# 2228_Emetteur_Alimentation.net
KiCad netlist of a schematic drawn in Altium Designer
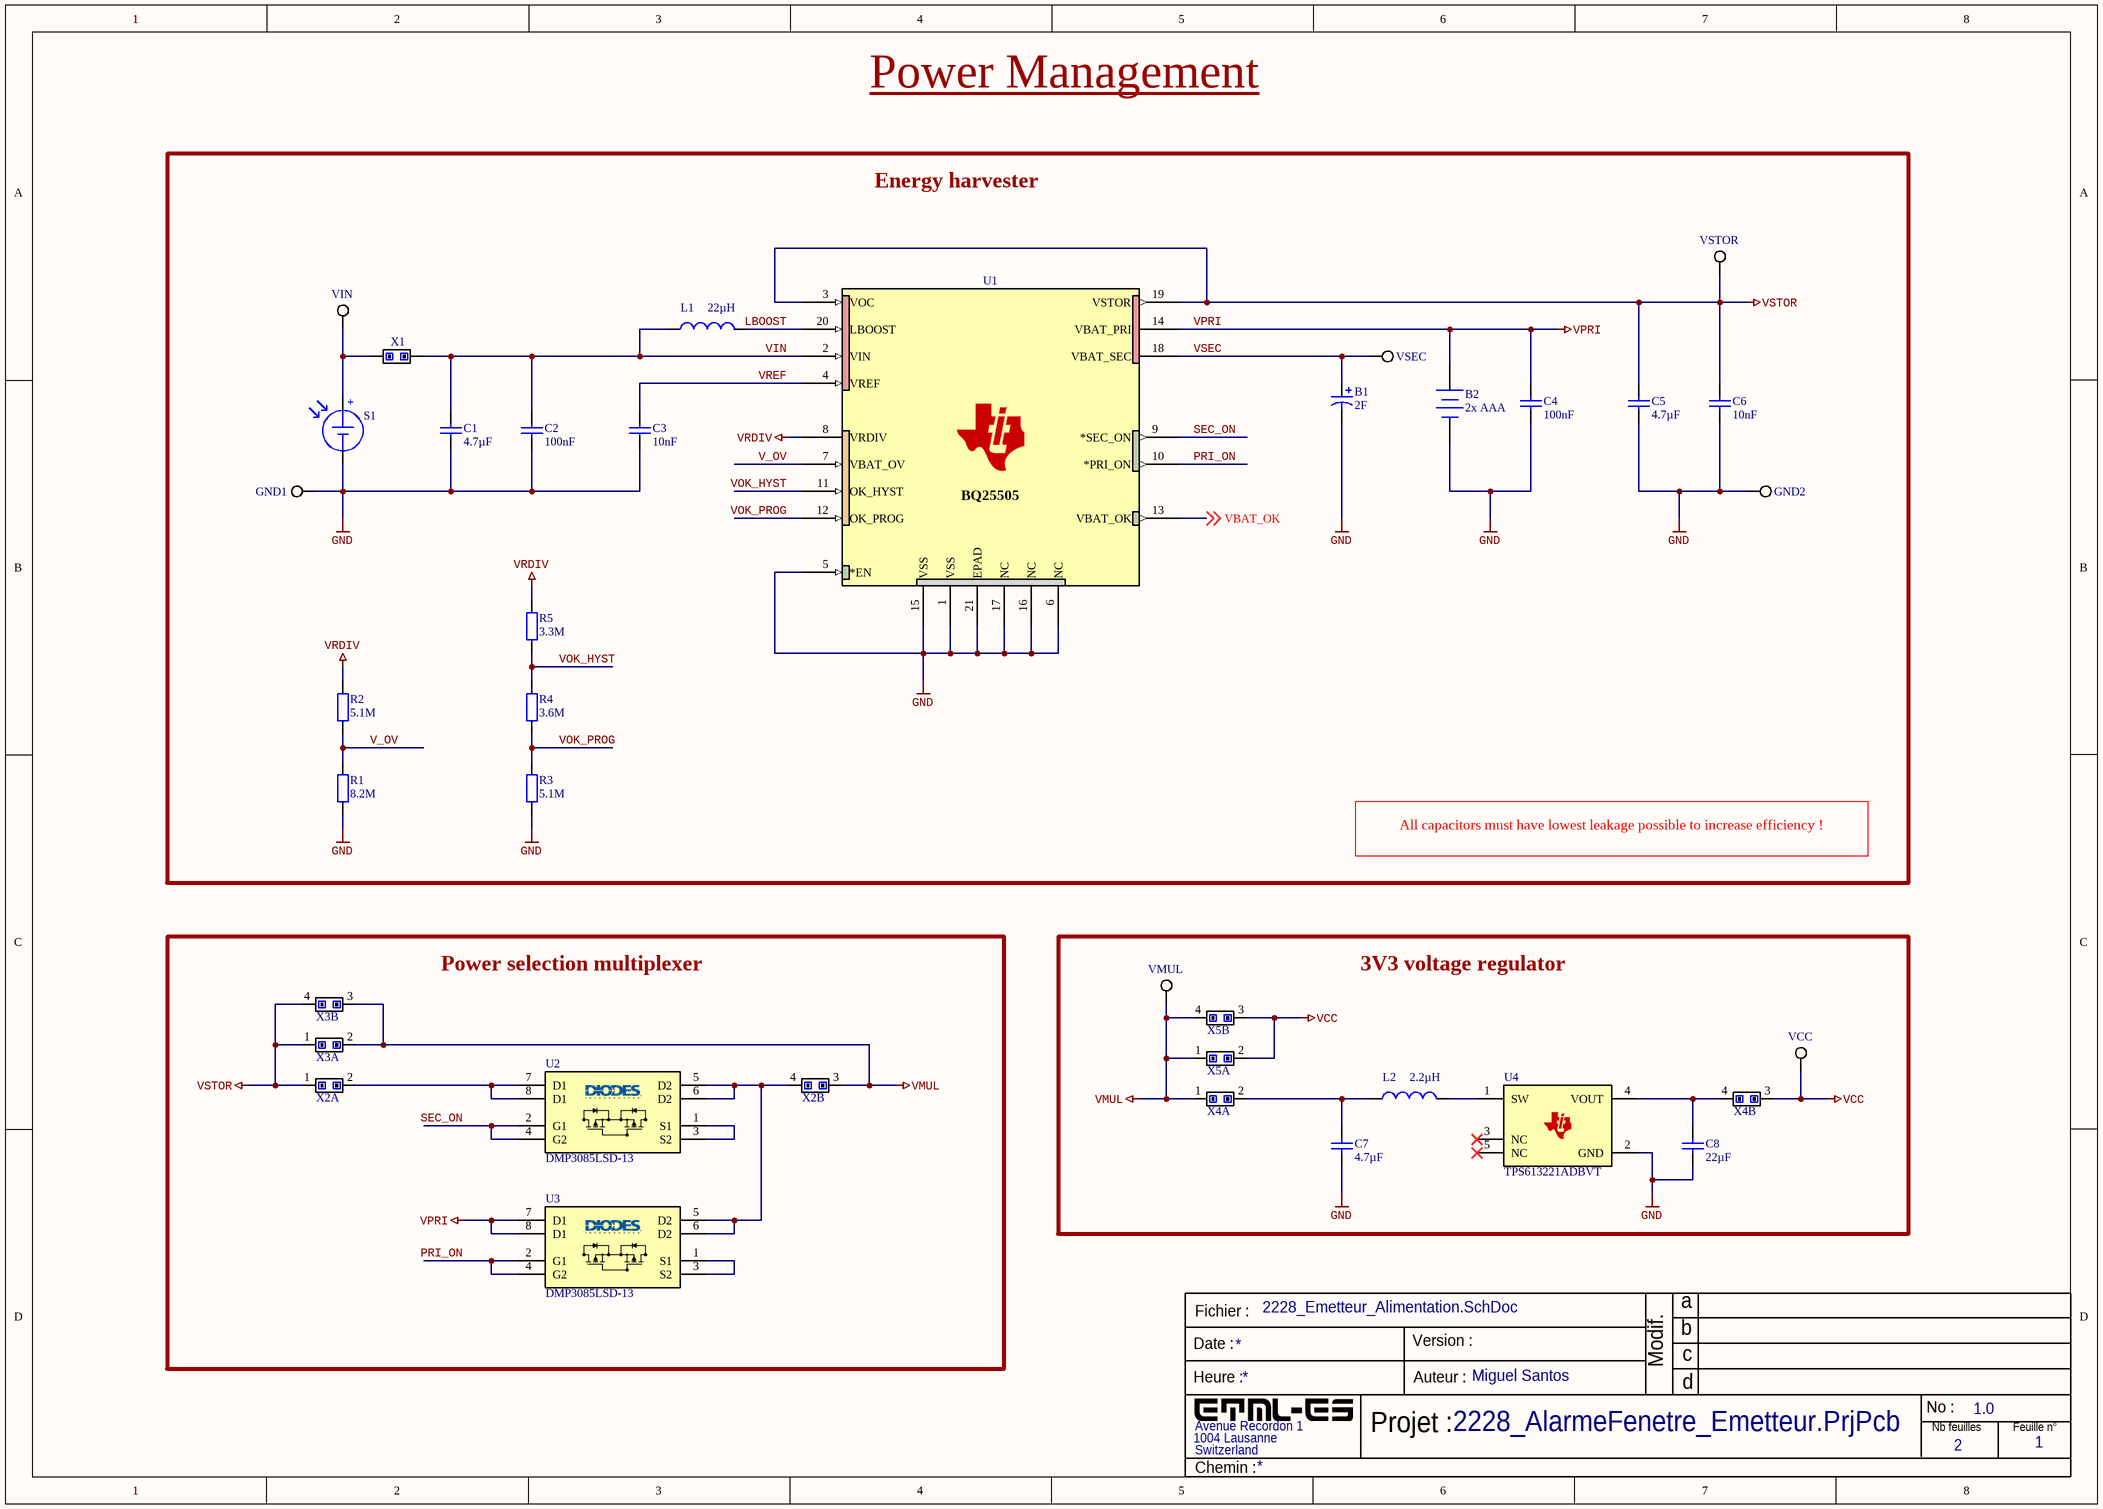
[diagram p0: 2228_Emetteur_Alimentation.SchDoc]

(export (version "E")
  (design (tool "Eeschema 10.0.6"))
  (components
    (comp (ref "B1")
      (value "2F")
      (footprint "2228_AlarmeFenetre_Footprints:SuperCap")
      (description "Polarized SuperCapacitor (Radial)")
      (fields (field (name "Comment") "SUPERCAP"))
      (libsource (lib "2228_AlarmeFenetre_Symbols") (part "SUPERCAP"))
    )
    (comp (ref "B2")
      (value "2x AAA")
      (footprint "WE_2PINS")
      (description "Multicell Battery")
      (libsource (lib "2228_AlarmeFenetre_Symbols") (part "Battery"))
    )
    (comp (ref "C1")
      (value "4.7µF")
      (footprint "CAP_0805")
      (description "Capacitor")
      (fields (field (name "Comment") "CAP_SMD"))
      (libsource (lib "2228_AlarmeFenetre_Symbols") (part "CAP_SMD"))
    )
    (comp (ref "C2")
      (value "100nF")
      (footprint "CAP_0805")
      (description "Capacitor")
      (fields (field (name "Comment") "CAP_SMD"))
      (libsource (lib "2228_AlarmeFenetre_Symbols") (part "CAP_SMD"))
    )
    (comp (ref "C3")
      (value "10nF")
      (footprint "CAP_0805")
      (description "Capacitor")
      (fields (field (name "Comment") "CAP_SMD"))
      (libsource (lib "2228_AlarmeFenetre_Symbols") (part "CAP_SMD"))
    )
    (comp (ref "C4")
      (value "100nF")
      (footprint "CAP_0805")
      (description "Capacitor")
      (fields (field (name "Comment") "CAP_SMD"))
      (libsource (lib "2228_AlarmeFenetre_Symbols") (part "CAP_SMD"))
    )
    (comp (ref "C5")
      (value "4.7µF")
      (footprint "CAP_0805")
      (description "Capacitor")
      (fields (field (name "Comment") "CAP_SMD"))
      (libsource (lib "2228_AlarmeFenetre_Symbols") (part "CAP_SMD"))
    )
    (comp (ref "C6")
      (value "10nF")
      (footprint "CAP_0805")
      (description "Capacitor")
      (fields (field (name "Comment") "CAP_SMD"))
      (libsource (lib "2228_AlarmeFenetre_Symbols") (part "CAP_SMD"))
    )
    (comp (ref "C7")
      (value "4.7µF")
      (footprint "CAP_0805")
      (description "Capacitor")
      (fields (field (name "Comment") "CAP_SMD"))
      (libsource (lib "2228_AlarmeFenetre_Symbols") (part "CAP_SMD"))
    )
    (comp (ref "C8")
      (value "22µF")
      (footprint "CAP_0805")
      (description "Capacitor")
      (fields (field (name "Comment") "CAP_SMD"))
      (libsource (lib "2228_AlarmeFenetre_Symbols") (part "CAP_SMD"))
    )
    (comp (ref "GND1")
      (value "5019")
      (footprint "KSTN-5019_V")
      (description "Test Point, 1 Position SMD, RoHS, Tape and Reel")
      (libsource (lib "Altium Content Vault") (part "TESTPOINT_WHITE"))
    )
    (comp (ref "GND2")
      (value "5019")
      (footprint "KSTN-5019_V")
      (description "Test Point, 1 Position SMD, RoHS, Tape and Reel")
      (libsource (lib "Altium Content Vault") (part "TESTPOINT_WHITE"))
    )
    (comp (ref "L1")
      (value "22µH")
      (footprint "WE-LQFS_4828")
      (description "Inductor SMD")
      (fields (field (name "Comment") "IND_SMD"))
      (libsource (lib "2228_AlarmeFenetre_Symbols") (part "IND_SMD"))
    )
    (comp (ref "L2")
      (value "2.2µH")
      (footprint "IND_0805")
      (description "Inductor SMD")
      (fields (field (name "Comment") "IND_SMD"))
      (libsource (lib "2228_AlarmeFenetre_Symbols") (part "IND_SMD"))
    )
    (comp (ref "R1")
      (value "8.2M")
      (footprint "RES_0805")
      (fields (field (name "Comment") "RES_SMD"))
      (libsource (lib "2228_AlarmeFenetre_Symbols") (part "RES_SMD"))
    )
    (comp (ref "R2")
      (value "5.1M")
      (footprint "RES_0805")
      (fields (field (name "Comment") "RES_SMD"))
      (libsource (lib "2228_AlarmeFenetre_Symbols") (part "RES_SMD"))
    )
    (comp (ref "R3")
      (value "5.1M")
      (footprint "RES_0805")
      (fields (field (name "Comment") "RES_SMD"))
      (libsource (lib "2228_AlarmeFenetre_Symbols") (part "RES_SMD"))
    )
    (comp (ref "R4")
      (value "3.6M")
      (footprint "RES_0805")
      (fields (field (name "Comment") "RES_SMD"))
      (libsource (lib "2228_AlarmeFenetre_Symbols") (part "RES_SMD"))
    )
    (comp (ref "R5")
      (value "3.3M")
      (footprint "RES_0805")
      (fields (field (name "Comment") "RES_SMD"))
      (libsource (lib "2228_AlarmeFenetre_Symbols") (part "RES_SMD"))
    )
    (comp (ref "S1")
      (value "Solar_Cell")
      (footprint "KXOB25-05X3F-TR")
      (description "Anysolar KXOB25-05X3F")
      (fields (field (name "MANUFACTURER") "Anysolar"))
      (libsource (lib "2228_AlarmeFenetre_Symbols") (part "Solar_Cell"))
    )
    (comp (ref "U1")
      (value "BQ25505")
      (footprint "2228_AlarmeFenetre_Footprints:QFN_25505")
      (description "Low power energy harvester")
      (fields (field (name "MANUFACTURER") "Texas Instruments"))
      (libsource (lib "2228_AlarmeFenetre_Symbols") (part "BQ25505RGRR"))
    )
    (comp (ref "U2")
      (value "DMP3085LSD-13")
      (footprint "2228_AlarmeFenetre_Footprints:SO-8")
      (fields (field (name "MANUFACTURER") "Diodes Inc"))
      (libsource (lib "2228_AlarmeFenetre_Symbols") (part "DMP3085LSD-13"))
    )
    (comp (ref "U3")
      (value "DMP3085LSD-13")
      (footprint "2228_AlarmeFenetre_Footprints:SO-8")
      (fields (field (name "MANUFACTURER") "Diodes Inc"))
      (libsource (lib "2228_AlarmeFenetre_Symbols") (part "DMP3085LSD-13"))
    )
    (comp (ref "U4")
      (value "TPS613221ADBVT")
      (footprint "2228_AlarmeFenetre_Footprints:SOT95P280X145-5N")
      (fields (field (name "MANUFACTURER") "Texas Instruments"))
      (libsource (lib "2228_AlarmeFenetre_Symbols") (part "TPS613221ADBVT"))
    )
    (comp (ref "VCC")
      (value "5019")
      (footprint "KSTN-5019_V")
      (description "Test Point, 1 Position SMD, RoHS, Tape and Reel")
      (libsource (lib "Altium Content Vault") (part "TESTPOINT_WHITE"))
    )
    (comp (ref "VIN")
      (value "5019")
      (footprint "KSTN-5019_V")
      (description "Test Point, 1 Position SMD, RoHS, Tape and Reel")
      (libsource (lib "Altium Content Vault") (part "TESTPOINT_WHITE"))
    )
    (comp (ref "VMUL")
      (value "5019")
      (footprint "KSTN-5019_V")
      (description "Test Point, 1 Position SMD, RoHS, Tape and Reel")
      (libsource (lib "Altium Content Vault") (part "TESTPOINT_WHITE"))
    )
    (comp (ref "VSEC")
      (value "5019")
      (footprint "KSTN-5019_V")
      (description "Test Point, 1 Position SMD, RoHS, Tape and Reel")
      (libsource (lib "Altium Content Vault") (part "TESTPOINT_WHITE"))
    )
    (comp (ref "VSTOR")
      (value "5019")
      (footprint "KSTN-5019_V")
      (description "Test Point, 1 Position SMD, RoHS, Tape and Reel")
      (libsource (lib "Altium Content Vault") (part "TESTPOINT_WHITE"))
    )
    (comp (ref "X1")
      (value "2PIN_HEADER")
      (footprint "HEADER_2PINS")
      (libsource (lib "2228_AlarmeFenetre_Symbols") (part "2PIN_HEADER"))
    )
    (comp (ref "X2")
      (value "2X2PIN_HEADER")
      (footprint "2x2_HEADER")
      (libsource (lib "") (part "2X2PIN_HEADER_1"))
    )
    (comp (ref "X3")
      (value "2X2PIN_HEADER")
      (footprint "2x2_HEADER")
      (libsource (lib "") (part "2X2PIN_HEADER_1"))
    )
    (comp (ref "X4")
      (value "2X2PIN_HEADER")
      (footprint "2x2_HEADER")
      (libsource (lib "") (part "2X2PIN_HEADER_1"))
    )
    (comp (ref "X5")
      (value "2X2PIN_HEADER")
      (footprint "2x2_HEADER")
      (libsource (lib "2228_AlarmeFenetre_Symbols") (part "2X2PIN_HEADER"))
    )
  )
  (nets
    (net (code "1") (name "/LBOOST") (class "Default")
      (node (ref "L1") (pin "2") (pinfunction "2_2") (pintype "passive"))
      (node (ref "U1") (pin "20") (pinfunction "LBOOST_20") (pintype "input"))
    )
    (net (code "2") (name "/PRI_ON") (class "Default")
      (node (ref "U1") (pin "10") (pinfunction "*PRI_ON_10") (pintype "output"))
      (node (ref "U3") (pin "2") (pinfunction "G1_2") (pintype "passive"))
      (node (ref "U3") (pin "4") (pinfunction "G2_4") (pintype "passive"))
    )
    (net (code "3") (name "/SEC_ON") (class "Default")
      (node (ref "U1") (pin "9") (pinfunction "*SEC_ON_9") (pintype "output"))
      (node (ref "U2") (pin "2") (pinfunction "G1_2") (pintype "passive"))
      (node (ref "U2") (pin "4") (pinfunction "G2_4") (pintype "passive"))
    )
    (net (code "4") (name "/VIN") (class "Default")
      (node (ref "C1") (pin "2") (pinfunction "2_2") (pintype "passive"))
      (node (ref "C2") (pin "2") (pinfunction "2_2") (pintype "passive"))
      (node (ref "L1") (pin "1") (pinfunction "1_1") (pintype "passive"))
      (node (ref "U1") (pin "2") (pinfunction "VIN_2") (pintype "input"))
      (node (ref "X1") (pin "2") (pinfunction "2_2") (pintype "passive"))
    )
    (net (code "5") (name "/VOK_HYST") (class "Default")
      (node (ref "R4") (pin "1") (pinfunction "1_1") (pintype "passive"))
      (node (ref "R5") (pin "2") (pinfunction "2_2") (pintype "passive"))
      (node (ref "U1") (pin "11") (pinfunction "OK_HYST_11") (pintype "input"))
    )
    (net (code "6") (name "/VOK_PROG") (class "Default")
      (node (ref "R3") (pin "1") (pinfunction "1_1") (pintype "passive"))
      (node (ref "R4") (pin "2") (pinfunction "2_2") (pintype "passive"))
      (node (ref "U1") (pin "12") (pinfunction "OK_PROG_12") (pintype "input"))
    )
    (net (code "7") (name "/VREF") (class "Default")
      (node (ref "C3") (pin "1") (pinfunction "1_1") (pintype "passive"))
      (node (ref "U1") (pin "4") (pinfunction "VREF_4") (pintype "input"))
    )
    (net (code "8") (name "/VSEC") (class "Default")
      (node (ref "B1") (pin "1") (pinfunction "1_1") (pintype "passive"))
      (node (ref "U1") (pin "18") (pinfunction "VBAT_SEC_18") (pintype "power_in"))
      (node (ref "VSEC") (pin "1") (pinfunction "1_1") (pintype "passive"))
    )
    (net (code "9") (name "/V_OV") (class "Default")
      (node (ref "R1") (pin "1") (pinfunction "1_1") (pintype "passive"))
      (node (ref "R2") (pin "2") (pinfunction "2_2") (pintype "passive"))
      (node (ref "U1") (pin "7") (pinfunction "VBAT_OV_7") (pintype "input"))
    )
    (net (code "10") (name "GND") (class "Default")
      (node (ref "B1") (pin "2") (pinfunction "2_2") (pintype "passive"))
      (node (ref "B2") (pin "2") (pinfunction "2_2") (pintype "passive"))
      (node (ref "C1") (pin "1") (pinfunction "1_1") (pintype "passive"))
      (node (ref "C2") (pin "1") (pinfunction "1_1") (pintype "passive"))
      (node (ref "C3") (pin "2") (pinfunction "2_2") (pintype "passive"))
      (node (ref "C4") (pin "1") (pinfunction "1_1") (pintype "passive"))
      (node (ref "C5") (pin "1") (pinfunction "1_1") (pintype "passive"))
      (node (ref "C6") (pin "1") (pinfunction "1_1") (pintype "passive"))
      (node (ref "C7") (pin "1") (pinfunction "1_1") (pintype "passive"))
      (node (ref "C8") (pin "1") (pinfunction "1_1") (pintype "passive"))
      (node (ref "GND1") (pin "1") (pinfunction "1_1") (pintype "passive"))
      (node (ref "GND2") (pin "1") (pinfunction "1_1") (pintype "passive"))
      (node (ref "R1") (pin "2") (pinfunction "2_2") (pintype "passive"))
      (node (ref "R3") (pin "2") (pinfunction "2_2") (pintype "passive"))
      (node (ref "S1") (pin "2") (pinfunction "-_2") (pintype "power_in"))
      (node (ref "U1") (pin "1") (pinfunction "VSS_1") (pintype "power_in"))
      (node (ref "U1") (pin "15") (pinfunction "VSS_15") (pintype "power_in"))
      (node (ref "U1") (pin "16") (pinfunction "NC_16") (pintype "passive"))
      (node (ref "U1") (pin "17") (pinfunction "NC_17") (pintype "passive"))
      (node (ref "U1") (pin "21") (pinfunction "EPAD_21") (pintype "passive"))
      (node (ref "U1") (pin "5") (pinfunction "*EN_5") (pintype "input"))
      (node (ref "U1") (pin "6") (pinfunction "NC_6") (pintype "passive"))
      (node (ref "U4") (pin "2") (pinfunction "GND_2") (pintype "power_in"))
    )
    (net (code "11") (name "Net-(C7-Pad2)") (class "Default")
      (node (ref "C7") (pin "2") (pinfunction "2_2") (pintype "passive"))
      (node (ref "L2") (pin "1") (pinfunction "1_1") (pintype "passive"))
      (node (ref "X4") (pin "2") (pinfunction "2_2") (pintype "passive"))
    )
    (net (code "12") (name "Net-(S1-+)") (class "Default")
      (node (ref "S1") (pin "1") (pinfunction "+_1") (pintype "power_in"))
      (node (ref "VIN") (pin "1") (pinfunction "1_1") (pintype "passive"))
      (node (ref "X1") (pin "1") (pinfunction "1_1") (pintype "passive"))
    )
    (net (code "13") (name "Net-(U2-D1-Pad7)") (class "Default")
      (node (ref "U2") (pin "7") (pinfunction "D1_7") (pintype "passive"))
      (node (ref "U2") (pin "8") (pinfunction "D1_8") (pintype "passive"))
      (node (ref "X2") (pin "2") (pinfunction "2_2") (pintype "passive"))
    )
    (net (code "14") (name "Net-(U2-D2-Pad5)") (class "Default")
      (node (ref "U2") (pin "5") (pinfunction "D2_5") (pintype "passive"))
      (node (ref "U2") (pin "6") (pinfunction "D2_6") (pintype "passive"))
      (node (ref "U3") (pin "5") (pinfunction "D2_5") (pintype "passive"))
      (node (ref "U3") (pin "6") (pinfunction "D2_6") (pintype "passive"))
      (node (ref "X2") (pin "4") (pinfunction "4_4") (pintype "passive"))
    )
    (net (code "15") (name "Net-(U2-S1)") (class "Default")
      (node (ref "U2") (pin "1") (pinfunction "S1_1") (pintype "passive"))
      (node (ref "U2") (pin "3") (pinfunction "S2_3") (pintype "passive"))
    )
    (net (code "16") (name "Net-(U3-S1)") (class "Default")
      (node (ref "U3") (pin "1") (pinfunction "S1_1") (pintype "passive"))
      (node (ref "U3") (pin "3") (pinfunction "S2_3") (pintype "passive"))
    )
    (net (code "17") (name "Net-(U4-SW)") (class "Default")
      (node (ref "L2") (pin "2") (pinfunction "2_2") (pintype "passive"))
      (node (ref "U4") (pin "1") (pinfunction "SW_1") (pintype "power_in"))
    )
    (net (code "18") (name "Net-(U4-VOUT)") (class "Default")
      (node (ref "C8") (pin "2") (pinfunction "2_2") (pintype "passive"))
      (node (ref "U4") (pin "4") (pinfunction "VOUT_4") (pintype "power_in"))
      (node (ref "X4") (pin "4") (pinfunction "4_4") (pintype "passive"))
    )
    (net (code "19") (name "VBAT_OK") (class "Default")
      (node (ref "U1") (pin "13") (pinfunction "VBAT_OK_13") (pintype "output"))
    )
    (net (code "20") (name "VCC") (class "Default")
      (node (ref "VCC") (pin "1") (pinfunction "1_1") (pintype "passive"))
      (node (ref "X4") (pin "3") (pinfunction "3_3") (pintype "passive"))
      (node (ref "X5") (pin "2") (pinfunction "2_2") (pintype "passive"))
      (node (ref "X5") (pin "3") (pinfunction "3_3") (pintype "passive"))
    )
    (net (code "21") (name "VMUL") (class "Default")
      (node (ref "VMUL") (pin "1") (pinfunction "1_1") (pintype "passive"))
      (node (ref "X2") (pin "3") (pinfunction "3_3") (pintype "passive"))
      (node (ref "X3") (pin "2") (pinfunction "2_2") (pintype "passive"))
      (node (ref "X3") (pin "3") (pinfunction "3_3") (pintype "passive"))
      (node (ref "X4") (pin "1") (pinfunction "1_1") (pintype "passive"))
      (node (ref "X5") (pin "1") (pinfunction "1_1") (pintype "passive"))
      (node (ref "X5") (pin "4") (pinfunction "4_4") (pintype "passive"))
    )
    (net (code "22") (name "VPRI") (class "Default")
      (node (ref "B2") (pin "1") (pinfunction "1_1") (pintype "passive"))
      (node (ref "C4") (pin "2") (pinfunction "2_2") (pintype "passive"))
      (node (ref "U1") (pin "14") (pinfunction "VBAT_PRI_14") (pintype "power_in"))
      (node (ref "U3") (pin "7") (pinfunction "D1_7") (pintype "passive"))
      (node (ref "U3") (pin "8") (pinfunction "D1_8") (pintype "passive"))
    )
    (net (code "23") (name "VRDIV") (class "Default")
      (node (ref "R2") (pin "1") (pinfunction "1_1") (pintype "passive"))
      (node (ref "R5") (pin "1") (pinfunction "1_1") (pintype "passive"))
      (node (ref "U1") (pin "8") (pinfunction "VRDIV_8") (pintype "power_in"))
    )
    (net (code "24") (name "VSTOR") (class "Default")
      (node (ref "C5") (pin "2") (pinfunction "2_2") (pintype "passive"))
      (node (ref "C6") (pin "2") (pinfunction "2_2") (pintype "passive"))
      (node (ref "U1") (pin "19") (pinfunction "VSTOR_19") (pintype "output"))
      (node (ref "U1") (pin "3") (pinfunction "VOC_3") (pintype "input"))
      (node (ref "VSTOR") (pin "1") (pinfunction "1_1") (pintype "passive"))
      (node (ref "X2") (pin "1") (pinfunction "1_1") (pintype "passive"))
      (node (ref "X3") (pin "1") (pinfunction "1_1") (pintype "passive"))
      (node (ref "X3") (pin "4") (pinfunction "4_4") (pintype "passive"))
    )
    (net (code "25") (name "unconnected-(U4-NC-Pad3)") (class "Default")
      (node (ref "U4") (pin "3") (pinfunction "NC_3") (pintype "passive+no_connect"))
    )
    (net (code "26") (name "unconnected-(U4-NC-Pad5)") (class "Default")
      (node (ref "U4") (pin "5") (pinfunction "NC_5") (pintype "passive+no_connect"))
    )
  )
)
